# HARDCAL1_REVA_PG2.net
KiCad netlist of a schematic drawn in Altium Designer
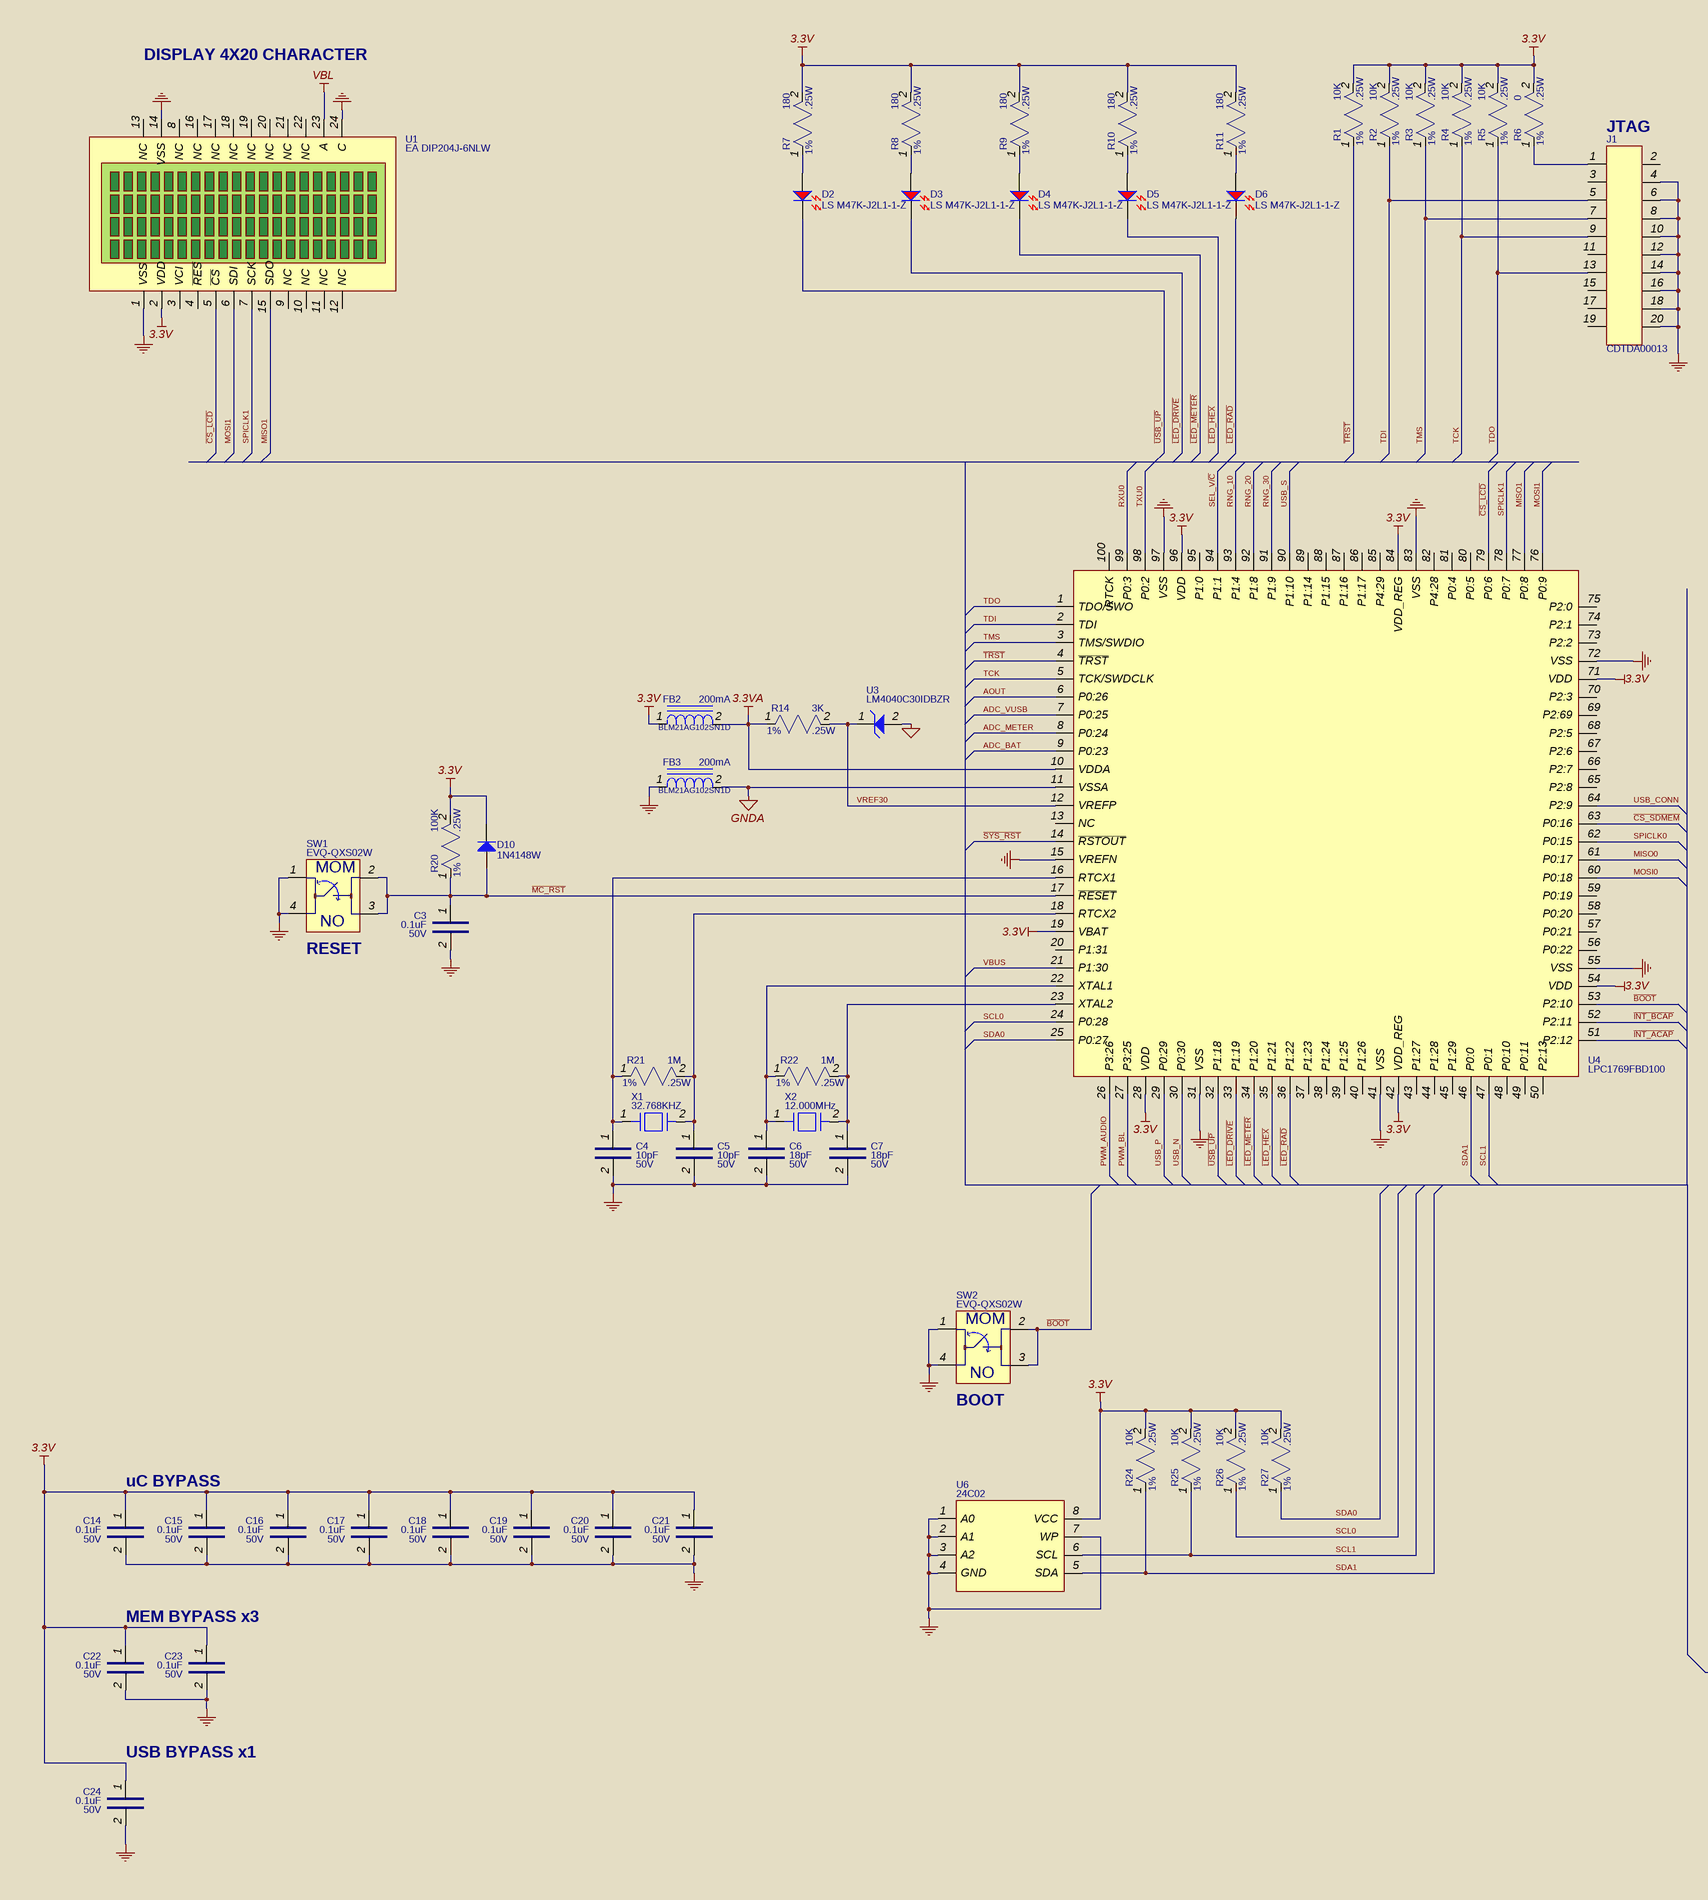
[diagram p0: HARDCAL1_REVA_PG2.SchDoc, left]
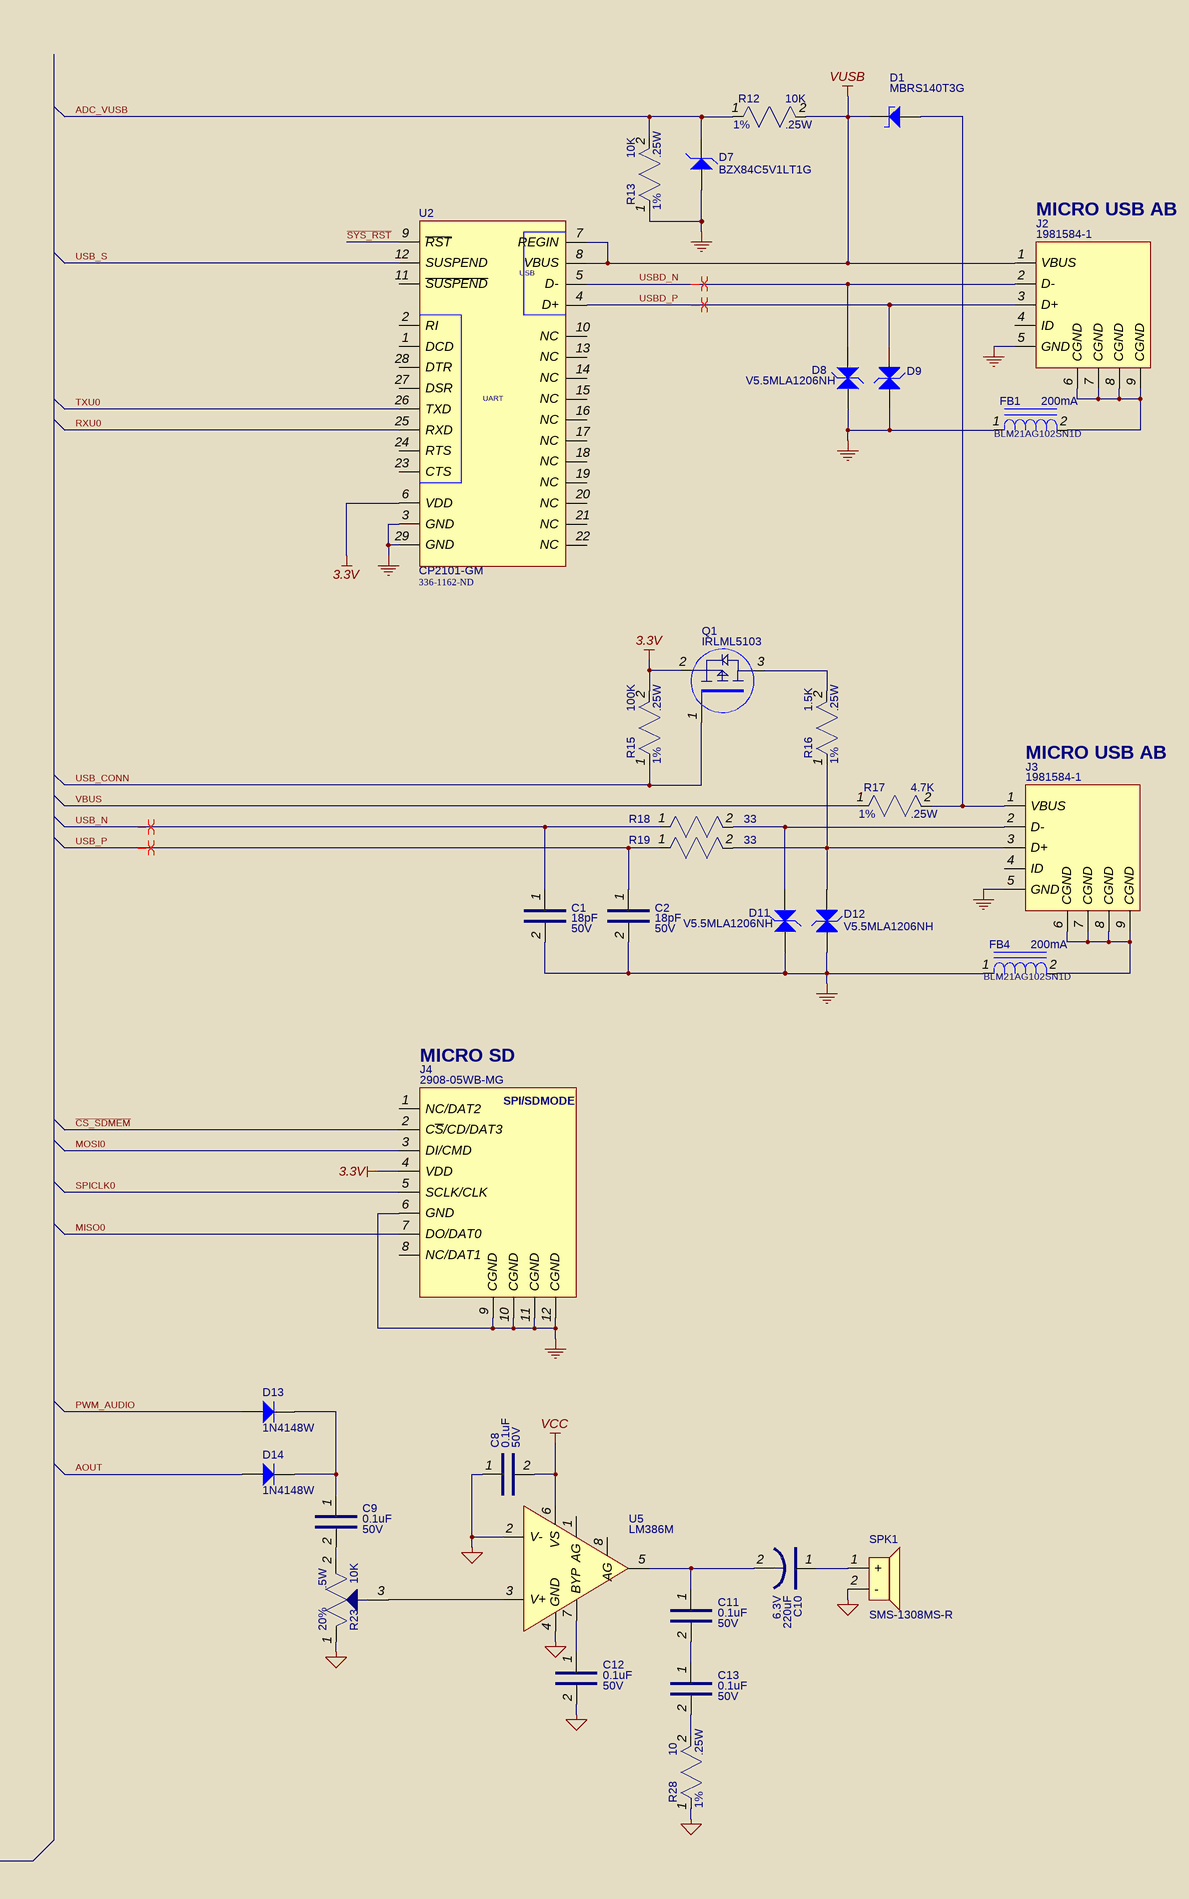
[diagram p1: HARDCAL1_REVA_PG2.SchDoc, right]

(export (version "E")
  (design (tool "Eeschema 10.0.6"))
  (components
    (comp (ref "C1")
      (value "18pF")
      (footprint "3216[1206] - TAN COLOR")
      (description "CAP, CERAMIC, NPO, 18PF, 50V, 1206, 5%, RoHS")
      (fields (field (name "MFG") "YAGEO") (field (name "TOLERANCE") "10%") (field (name "VOLTAGE") "50V"))
      (libsource (lib "HabLib") (part "CDECA00095"))
    )
    (comp (ref "C2")
      (value "18pF")
      (footprint "3216[1206] - TAN COLOR")
      (description "CAP, CERAMIC, NPO, 18PF, 50V, 1206, 5%, RoHS")
      (fields (field (name "MFG") "YAGEO") (field (name "TOLERANCE") "10%") (field (name "VOLTAGE") "50V"))
      (libsource (lib "HabLib") (part "CDECA00095"))
    )
    (comp (ref "C3")
      (value "0.1uF")
      (footprint "3216[1206] - TAN COLOR")
      (description "CAP, CERAMIC CHIP 0.1UF 10% 50V X7R ROHS")
      (fields (field (name "MFG") "AVX") (field (name "TOLERANCE") "10%") (field (name "VOLTAGE") "50V"))
      (libsource (lib "HabLib") (part "CDECA00070"))
    )
    (comp (ref "C4")
      (value "10pF")
      (footprint "3216[1206] - TAN COLOR")
      (description "CAP, CERAMIC, NPO, 10PF, 50V, 1206, 5%, RoHS")
      (fields (field (name "MFG") "AVX") (field (name "TOLERANCE") "10%") (field (name "VOLTAGE") "50V"))
      (libsource (lib "HabLib") (part "CDECA00143"))
    )
    (comp (ref "C5")
      (value "10pF")
      (footprint "3216[1206] - TAN COLOR")
      (description "CAP, CERAMIC, NPO, 10PF, 50V, 1206, 5%, RoHS")
      (fields (field (name "MFG") "AVX") (field (name "TOLERANCE") "10%") (field (name "VOLTAGE") "50V"))
      (libsource (lib "HabLib") (part "CDECA00143"))
    )
    (comp (ref "C6")
      (value "18pF")
      (footprint "3216[1206] - TAN COLOR")
      (description "CAP, CERAMIC, NPO, 18PF, 50V, 1206, 5%, RoHS")
      (fields (field (name "MFG") "YAGEO") (field (name "TOLERANCE") "10%") (field (name "VOLTAGE") "50V"))
      (libsource (lib "HabLib") (part "CDECA00095"))
    )
    (comp (ref "C7")
      (value "18pF")
      (footprint "3216[1206] - TAN COLOR")
      (description "CAP, CERAMIC, NPO, 18PF, 50V, 1206, 5%, RoHS")
      (fields (field (name "MFG") "YAGEO") (field (name "TOLERANCE") "10%") (field (name "VOLTAGE") "50V"))
      (libsource (lib "HabLib") (part "CDECA00095"))
    )
    (comp (ref "C8")
      (value "0.1uF")
      (footprint "3216[1206] - TAN COLOR")
      (description "CAP, CERAMIC CHIP 0.1UF 10% 50V X7R ROHS")
      (fields (field (name "MFG") "AVX") (field (name "TOLERANCE") "10%") (field (name "VOLTAGE") "50V"))
      (libsource (lib "HabLib") (part "CDECA00070"))
    )
    (comp (ref "C9")
      (value "0.1uF")
      (footprint "3216[1206] - TAN COLOR")
      (description "CAP, CERAMIC CHIP 0.1UF 10% 50V X7R ROHS")
      (fields (field (name "MFG") "AVX") (field (name "TOLERANCE") "10%") (field (name "VOLTAGE") "50V"))
      (libsource (lib "HabLib") (part "CDECA00070"))
    )
    (comp (ref "C10")
      (value "220uF")
      (footprint "CAP_TANT_3528")
      (description "CAP, TANT, 220UF, 6.3V, 20%, LOW ESR, 3528, ROHS")
      (fields (field (name "MFG") "KEMET") (field (name "TOLERANCE") "20%") (field (name "VOLTAGE") "6.3V"))
      (libsource (lib "HabLib") (part "CDECA00139_2"))
    )
    (comp (ref "C11")
      (value "0.1uF")
      (footprint "3216[1206] - TAN COLOR")
      (description "CAP, CERAMIC CHIP 0.1UF 10% 50V X7R ROHS")
      (fields (field (name "MFG") "AVX") (field (name "TOLERANCE") "10%") (field (name "VOLTAGE") "50V"))
      (libsource (lib "HabLib") (part "CDECA00070"))
    )
    (comp (ref "C12")
      (value "0.1uF")
      (footprint "3216[1206] - TAN COLOR")
      (description "CAP, CERAMIC CHIP 0.1UF 10% 50V X7R ROHS")
      (fields (field (name "MFG") "AVX") (field (name "TOLERANCE") "10%") (field (name "VOLTAGE") "50V"))
      (libsource (lib "HabLib") (part "CDECA00070"))
    )
    (comp (ref "C13")
      (value "0.1uF")
      (footprint "3216[1206] - TAN COLOR")
      (description "CAP, CERAMIC CHIP 0.1UF 10% 50V X7R ROHS")
      (fields (field (name "MFG") "AVX") (field (name "TOLERANCE") "10%") (field (name "VOLTAGE") "50V"))
      (libsource (lib "HabLib") (part "CDECA00070"))
    )
    (comp (ref "C14")
      (value "0.1uF")
      (footprint "3216[1206] - TAN COLOR")
      (description "CAP, CERAMIC CHIP 0.1UF 10% 50V X7R ROHS")
      (fields (field (name "MFG") "AVX") (field (name "TOLERANCE") "10%") (field (name "VOLTAGE") "50V"))
      (libsource (lib "HabLib") (part "CDECA00070"))
    )
    (comp (ref "C15")
      (value "0.1uF")
      (footprint "3216[1206] - TAN COLOR")
      (description "CAP, CERAMIC CHIP 0.1UF 10% 50V X7R ROHS")
      (fields (field (name "MFG") "AVX") (field (name "TOLERANCE") "10%") (field (name "VOLTAGE") "50V"))
      (libsource (lib "HabLib") (part "CDECA00070"))
    )
    (comp (ref "C16")
      (value "0.1uF")
      (footprint "3216[1206] - TAN COLOR")
      (description "CAP, CERAMIC CHIP 0.1UF 10% 50V X7R ROHS")
      (fields (field (name "MFG") "AVX") (field (name "TOLERANCE") "10%") (field (name "VOLTAGE") "50V"))
      (libsource (lib "HabLib") (part "CDECA00070"))
    )
    (comp (ref "C17")
      (value "0.1uF")
      (footprint "3216[1206] - TAN COLOR")
      (description "CAP, CERAMIC CHIP 0.1UF 10% 50V X7R ROHS")
      (fields (field (name "MFG") "AVX") (field (name "TOLERANCE") "10%") (field (name "VOLTAGE") "50V"))
      (libsource (lib "HabLib") (part "CDECA00070"))
    )
    (comp (ref "C18")
      (value "0.1uF")
      (footprint "3216[1206] - TAN COLOR")
      (description "CAP, CERAMIC CHIP 0.1UF 10% 50V X7R ROHS")
      (fields (field (name "MFG") "AVX") (field (name "TOLERANCE") "10%") (field (name "VOLTAGE") "50V"))
      (libsource (lib "HabLib") (part "CDECA00070"))
    )
    (comp (ref "C19")
      (value "0.1uF")
      (footprint "3216[1206] - TAN COLOR")
      (description "CAP, CERAMIC CHIP 0.1UF 10% 50V X7R ROHS")
      (fields (field (name "MFG") "AVX") (field (name "TOLERANCE") "10%") (field (name "VOLTAGE") "50V"))
      (libsource (lib "HabLib") (part "CDECA00070"))
    )
    (comp (ref "C20")
      (value "0.1uF")
      (footprint "3216[1206] - TAN COLOR")
      (description "CAP, CERAMIC CHIP 0.1UF 10% 50V X7R ROHS")
      (fields (field (name "MFG") "AVX") (field (name "TOLERANCE") "10%") (field (name "VOLTAGE") "50V"))
      (libsource (lib "HabLib") (part "CDECA00070"))
    )
    (comp (ref "C21")
      (value "0.1uF")
      (footprint "3216[1206] - TAN COLOR")
      (description "CAP, CERAMIC CHIP 0.1UF 10% 50V X7R ROHS")
      (fields (field (name "MFG") "AVX") (field (name "TOLERANCE") "10%") (field (name "VOLTAGE") "50V"))
      (libsource (lib "HabLib") (part "CDECA00070"))
    )
    (comp (ref "C22")
      (value "0.1uF")
      (footprint "3216[1206] - TAN COLOR")
      (description "CAP, CERAMIC CHIP 0.1UF 10% 50V X7R ROHS")
      (fields (field (name "MFG") "AVX") (field (name "TOLERANCE") "10%") (field (name "VOLTAGE") "50V"))
      (libsource (lib "HabLib") (part "CDECA00070"))
    )
    (comp (ref "C23")
      (value "0.1uF")
      (footprint "3216[1206] - TAN COLOR")
      (description "CAP, CERAMIC CHIP 0.1UF 10% 50V X7R ROHS")
      (fields (field (name "MFG") "AVX") (field (name "TOLERANCE") "10%") (field (name "VOLTAGE") "50V"))
      (libsource (lib "HabLib") (part "CDECA00070"))
    )
    (comp (ref "C24")
      (value "0.1uF")
      (footprint "3216[1206] - TAN COLOR")
      (description "CAP, CERAMIC CHIP 0.1UF 10% 50V X7R ROHS")
      (fields (field (name "MFG") "AVX") (field (name "TOLERANCE") "10%") (field (name "VOLTAGE") "50V"))
      (libsource (lib "HabLib") (part "CDECA00070"))
    )
    (comp (ref "D1")
      (value "MBRS140T3G")
      (footprint "DIODE_SMB")
      (description "Diode, Schottky rectifier, 40V, 1A, SMB package, Pb free")
      (fields
        (field (name "MFG") "ON SEMICONDUCTOR")
        (field (name "Comment") "CDEDA00019")
        (field (name "PUBLISHER") "Altium Limited")
      )
      (libsource (lib "HabLib") (part "CDEDA00019"))
    )
    (comp (ref "D2")
      (value "LS M47K-J2L1-1-Z")
      (footprint "OSRAM_XX_M47K")
      (description "DIODE,LED RED UNDER MOUNT SM VF=1.8 I=2MA ROHS")
      (fields (field (name "MFG") "OSRAM") (field (name "Comment") "CDELA00019_1"))
      (libsource (lib "HabLib") (part "CDELA00019_1"))
    )
    (comp (ref "D3")
      (value "LS M47K-J2L1-1-Z")
      (footprint "OSRAM_XX_M47K")
      (description "DIODE,LED RED UNDER MOUNT SM VF=1.8 I=2MA ROHS")
      (fields (field (name "MFG") "OSRAM") (field (name "Comment") "CDELA00019_1"))
      (libsource (lib "HabLib") (part "CDELA00019_1"))
    )
    (comp (ref "D4")
      (value "LS M47K-J2L1-1-Z")
      (footprint "OSRAM_XX_M47K")
      (description "DIODE,LED RED UNDER MOUNT SM VF=1.8 I=2MA ROHS")
      (fields (field (name "MFG") "OSRAM") (field (name "Comment") "CDELA00019_1"))
      (libsource (lib "HabLib") (part "CDELA00019_1"))
    )
    (comp (ref "D5")
      (value "LS M47K-J2L1-1-Z")
      (footprint "OSRAM_XX_M47K")
      (description "DIODE,LED RED UNDER MOUNT SM VF=1.8 I=2MA ROHS")
      (fields (field (name "MFG") "OSRAM") (field (name "Comment") "CDELA00019_1"))
      (libsource (lib "HabLib") (part "CDELA00019_1"))
    )
    (comp (ref "D6")
      (value "LS M47K-J2L1-1-Z")
      (footprint "OSRAM_XX_M47K")
      (description "DIODE,LED RED UNDER MOUNT SM VF=1.8 I=2MA ROHS")
      (fields (field (name "MFG") "OSRAM") (field (name "Comment") "CDELA00019_1"))
      (libsource (lib "HabLib") (part "CDELA00019_1"))
    )
    (comp (ref "D7")
      (value "BZX84C5V1LT1G")
      (footprint "SOT23 - TRANSISTOR")
      (description "DIODE, ZENER, 5.1V, 225MW, SOT-23, ROHS")
      (fields
        (field (name "MFG") "ON SEMICONDUCTOR")
        (field (name "Comment") "CDEDA00043")
        (field (name "PUBLISHER") "Altium Limited")
      )
      (libsource (lib "HabLib") (part "CDEDA00043"))
    )
    (comp (ref "D8")
      (value "V5.5MLA1206NH")
      (footprint "3216[1206]")
      (description "VARISTOR, TVS, 5.5VDC, 1206, 150A, .60J, RoHS")
      (fields (field (name "MFG") "LITTLEFUSE") (field (name "MANUFACTURER") "Littelfuse Inc"))
      (libsource (lib "HabLib") (part "CDEDA00037_1"))
    )
    (comp (ref "D9")
      (value "CDEDA00037_1")
      (footprint "3216[1206]")
      (description "VARISTOR, TVS, 5.5VDC, 1206, 150A, .60J, RoHS")
      (fields (field (name "MFG") "LITTLEFUSE") (field (name "MANUFACTURER") "Littelfuse Inc"))
      (libsource (lib "HabLib") (part "CDEDA00037_1"))
    )
    (comp (ref "D10")
      (value "1N4148W")
      (footprint "HabLib:SOD123")
      (description "DIODE, 150MA, 100V, SOD123")
      (fields
        (field (name "MFG") "DIODES INC")
        (field (name "Comment") "CDEDA00020")
        (field (name "PUBLISHER") "Altium Limited")
      )
      (libsource (lib "HabLib") (part "CDEDA00020"))
    )
    (comp (ref "D11")
      (value "V5.5MLA1206NH")
      (footprint "3216[1206]")
      (description "VARISTOR, TVS, 5.5VDC, 1206, 150A, .60J, RoHS")
      (fields (field (name "MFG") "LITTLEFUSE") (field (name "MANUFACTURER") "Littelfuse Inc"))
      (libsource (lib "HabLib") (part "CDEDA00037_1"))
    )
    (comp (ref "D12")
      (value "V5.5MLA1206NH")
      (footprint "3216[1206]")
      (description "VARISTOR, TVS, 5.5VDC, 1206, 150A, .60J, RoHS")
      (fields (field (name "MFG") "LITTLEFUSE") (field (name "MANUFACTURER") "Littelfuse Inc"))
      (libsource (lib "HabLib") (part "CDEDA00037_1"))
    )
    (comp (ref "D13")
      (value "1N4148W")
      (footprint "SOD123")
      (description "DIODE, 150MA, 100V, SOD123")
      (fields (field (name "MFG") "DIODES INC") (field (name "Comment") "CDEDA00020"))
      (libsource (lib "HabLib") (part "CDEDA00020"))
    )
    (comp (ref "D14")
      (value "1N4148W")
      (footprint "SOD123")
      (description "DIODE, 150MA, 100V, SOD123")
      (fields (field (name "MFG") "DIODES INC") (field (name "Comment") "CDEDA00020"))
      (libsource (lib "HabLib") (part "CDEDA00020"))
    )
    (comp (ref "FB1")
      (value "CDEVA00115")
      (footprint "2012[0805]")
      (description "FERRITE, 1KOHM AT 100MHZ, 220MA, .450DCR")
      (fields
        (field (name "MFG") "MURATA")
        (field (name "TOLERANCE") "10%")
        (field (name "MFG_PN") "BLM21AG102SN1D")
        (field (name "POWER") "200mA")
        (field (name "PUBLISHER") "Altium Limited")
      )
      (libsource (lib "HabLib") (part "CDEVA00115"))
    )
    (comp (ref "FB2")
      (value "CDEVA00115")
      (footprint "2012[0805]")
      (description "FERRITE, 1KOHM AT 100MHZ, 220MA, .450DCR")
      (fields
        (field (name "MFG") "MURATA")
        (field (name "TOLERANCE") "10%")
        (field (name "MFG_PN") "BLM21AG102SN1D")
        (field (name "POWER") "200mA")
        (field (name "PUBLISHER") "Altium Limited")
      )
      (libsource (lib "HabLib") (part "CDEVA00115"))
    )
    (comp (ref "FB3")
      (value "CDEVA00115")
      (footprint "2012[0805]")
      (description "FERRITE, 1KOHM AT 100MHZ, 220MA, .450DCR")
      (fields
        (field (name "MFG") "MURATA")
        (field (name "TOLERANCE") "10%")
        (field (name "MFG_PN") "BLM21AG102SN1D")
        (field (name "POWER") "200mA")
        (field (name "PUBLISHER") "Altium Limited")
      )
      (libsource (lib "HabLib") (part "CDEVA00115"))
    )
    (comp (ref "FB4")
      (value "CDEVA00115")
      (footprint "2012[0805]")
      (description "FERRITE, 1KOHM AT 100MHZ, 220MA, .450DCR")
      (fields
        (field (name "MFG") "MURATA")
        (field (name "TOLERANCE") "10%")
        (field (name "MFG_PN") "BLM21AG102SN1D")
        (field (name "POWER") "200mA")
        (field (name "PUBLISHER") "Altium Limited")
      )
      (libsource (lib "HabLib") (part "CDEVA00115"))
    )
    (comp (ref "J1")
      (value "CDTDA00013")
      (footprint "HDR_2X10_100MIL")
      (description "CONN, HDR, 2X10, 100MIL, TH, ROHS")
      (fields (field (name "MFG") "TYCO ELECTRONICS"))
      (libsource (lib "HabLib") (part "CDTDA00013"))
    )
    (comp (ref "J2")
      (value "1981584-1")
      (footprint "TYCO_1981584-1")
      (description "CONN, RCPTL MICRO USB TYPE AB, SM RA")
      (fields (field (name "MFG") "TYCO") (field (name "Comment") "CDTDA_1"))
      (libsource (lib "HabLib") (part "CDTDA_1"))
    )
    (comp (ref "J3")
      (value "1981584-1")
      (footprint "TYCO_1981584-1")
      (description "CONN, RCPTL MICRO USB TYPE AB, SM RA")
      (fields (field (name "MFG") "TYCO") (field (name "Comment") "CDTDA_1"))
      (libsource (lib "HabLib") (part "CDTDA_1"))
    )
    (comp (ref "J4")
      (value "2908-05WB-MG")
      (footprint "3M_2908-05WB-MG")
      (description "CONN, MICRO SD, SM, ROHS")
      (fields (field (name "MFG") "3M") (field (name "Comment") "CDTDA_2"))
      (libsource (lib "HabLib") (part "CDTDA_2"))
    )
    (comp (ref "Q1")
      (value "IRLML5103")
      (footprint "SOT23 - TRANSISTOR")
      (description "MOSFET P CHN, VDS=30V, RDSON = .6OHM, SOT 23")
      (fields
        (field (name "MFG") "INTERNATIONAL RECTIFIER")
        (field (name "Comment") "CDENA00031")
        (field (name "PUBLISHER") "Altium Limited")
      )
      (libsource (lib "HabLib") (part "CDENA00031"))
    )
    (comp (ref "R1")
      (value "10K")
      (footprint "HabLib:3216[1206]")
      (description "RESISTOR, CHIP 1206 10K OHM 1% 1/4W THICK FILM ROHS")
      (fields
        (field (name "MFG") "PANASONIC")
        (field (name "TOLERANCE") "1%")
        (field (name "POWER") ".25W")
        (field (name "Comment") "CDERA00170")
        (field (name "PUBLISHER") "Altium Limited")
      )
      (libsource (lib "HabLib") (part "CDERA00170"))
    )
    (comp (ref "R2")
      (value "10K")
      (footprint "HabLib:3216[1206]")
      (description "RESISTOR, CHIP 1206 10K OHM 1% 1/4W THICK FILM ROHS")
      (fields
        (field (name "MFG") "PANASONIC")
        (field (name "TOLERANCE") "1%")
        (field (name "POWER") ".25W")
        (field (name "Comment") "CDERA00170")
        (field (name "PUBLISHER") "Altium Limited")
      )
      (libsource (lib "HabLib") (part "CDERA00170"))
    )
    (comp (ref "R3")
      (value "10K")
      (footprint "HabLib:3216[1206]")
      (description "RESISTOR, CHIP 1206 10K OHM 1% 1/4W THICK FILM ROHS")
      (fields
        (field (name "MFG") "PANASONIC")
        (field (name "TOLERANCE") "1%")
        (field (name "POWER") ".25W")
        (field (name "Comment") "CDERA00170")
        (field (name "PUBLISHER") "Altium Limited")
      )
      (libsource (lib "HabLib") (part "CDERA00170"))
    )
    (comp (ref "R4")
      (value "10K")
      (footprint "HabLib:3216[1206]")
      (description "RESISTOR, CHIP 1206 10K OHM 1% 1/4W THICK FILM ROHS")
      (fields
        (field (name "MFG") "PANASONIC")
        (field (name "TOLERANCE") "1%")
        (field (name "POWER") ".25W")
        (field (name "Comment") "CDERA00170")
        (field (name "PUBLISHER") "Altium Limited")
      )
      (libsource (lib "HabLib") (part "CDERA00170"))
    )
    (comp (ref "R5")
      (value "10K")
      (footprint "HabLib:3216[1206]")
      (description "RESISTOR, CHIP 1206 10K OHM 1% 1/4W THICK FILM ROHS")
      (fields
        (field (name "MFG") "PANASONIC")
        (field (name "TOLERANCE") "1%")
        (field (name "POWER") ".25W")
        (field (name "Comment") "CDERA00170")
        (field (name "PUBLISHER") "Altium Limited")
      )
      (libsource (lib "HabLib") (part "CDERA00170"))
    )
    (comp (ref "R6")
      (value "0")
      (footprint "HABLIB:3216[1206]")
      (description "RESISTOR, CHIP 1206 0.0 OHM 1% 1/4W THICK FILM ROHS")
      (fields
        (field (name "MFG") "PANASONIC")
        (field (name "TOLERANCE") "1%")
        (field (name "POWER") ".25W")
        (field (name "Comment") "CDERA00181")
        (field (name "PUBLISHER") "Altium Limited")
      )
      (libsource (lib "HabLib") (part "CDERA00181"))
    )
    (comp (ref "R7")
      (value "180")
      (footprint "HABLIB:3216[1206]")
      (description "RESISTOR, CHIP 1206 180 OHM 1% 1/4W THICK FILM ROHS")
      (fields
        (field (name "MFG") "PANASONIC")
        (field (name "TOLERANCE") "1%")
        (field (name "POWER") ".25W")
        (field (name "Comment") "CDERA00192")
        (field (name "PUBLISHER") "Altium Limited")
      )
      (libsource (lib "HabLib") (part "CDERA00192"))
    )
    (comp (ref "R8")
      (value "180")
      (footprint "HABLIB:3216[1206]")
      (description "RESISTOR, CHIP 1206 180 OHM 1% 1/4W THICK FILM ROHS")
      (fields
        (field (name "MFG") "PANASONIC")
        (field (name "TOLERANCE") "1%")
        (field (name "POWER") ".25W")
        (field (name "Comment") "CDERA00192")
        (field (name "PUBLISHER") "Altium Limited")
      )
      (libsource (lib "HabLib") (part "CDERA00192"))
    )
    (comp (ref "R9")
      (value "180")
      (footprint "HABLIB:3216[1206]")
      (description "RESISTOR, CHIP 1206 180 OHM 1% 1/4W THICK FILM ROHS")
      (fields
        (field (name "MFG") "PANASONIC")
        (field (name "TOLERANCE") "1%")
        (field (name "POWER") ".25W")
        (field (name "Comment") "CDERA00192")
        (field (name "PUBLISHER") "Altium Limited")
      )
      (libsource (lib "HabLib") (part "CDERA00192"))
    )
    (comp (ref "R10")
      (value "180")
      (footprint "HABLIB:3216[1206]")
      (description "RESISTOR, CHIP 1206 180 OHM 1% 1/4W THICK FILM ROHS")
      (fields
        (field (name "MFG") "PANASONIC")
        (field (name "TOLERANCE") "1%")
        (field (name "POWER") ".25W")
        (field (name "Comment") "CDERA00192")
        (field (name "PUBLISHER") "Altium Limited")
      )
      (libsource (lib "HabLib") (part "CDERA00192"))
    )
    (comp (ref "R11")
      (value "180")
      (footprint "HABLIB:3216[1206]")
      (description "RESISTOR, CHIP 1206 180 OHM 1% 1/4W THICK FILM ROHS")
      (fields
        (field (name "MFG") "PANASONIC")
        (field (name "TOLERANCE") "1%")
        (field (name "POWER") ".25W")
        (field (name "Comment") "CDERA00192")
        (field (name "PUBLISHER") "Altium Limited")
      )
      (libsource (lib "HabLib") (part "CDERA00192"))
    )
    (comp (ref "R12")
      (value "10K")
      (footprint "HabLib:3216[1206]")
      (description "RESISTOR, CHIP 1206 10K OHM 1% 1/4W THICK FILM ROHS")
      (fields
        (field (name "MFG") "PANASONIC")
        (field (name "TOLERANCE") "1%")
        (field (name "POWER") ".25W")
        (field (name "Comment") "CDERA00170")
        (field (name "PUBLISHER") "Altium Limited")
      )
      (libsource (lib "HabLib") (part "CDERA00170"))
    )
    (comp (ref "R13")
      (value "10K")
      (footprint "HabLib:3216[1206]")
      (description "RESISTOR, CHIP 1206 10K OHM 1% 1/4W THICK FILM ROHS")
      (fields
        (field (name "MFG") "PANASONIC")
        (field (name "TOLERANCE") "1%")
        (field (name "POWER") ".25W")
        (field (name "Comment") "CDERA00170")
        (field (name "PUBLISHER") "Altium Limited")
      )
      (libsource (lib "HabLib") (part "CDERA00170"))
    )
    (comp (ref "R14")
      (value "3K")
      (footprint "HABLIB:3216[1206]")
      (description "RESISTOR, CHIP 1206 3K OHM 1% 1/4W THICK FILM ROHS")
      (fields
        (field (name "MFG") "PANASONIC")
        (field (name "TOLERANCE") "1%")
        (field (name "POWER") ".25W")
        (field (name "Comment") "CDERA00275_9")
        (field (name "PUBLISHER") "Altium Limited")
      )
      (libsource (lib "HabLib") (part "CDERA00275_9"))
    )
    (comp (ref "R15")
      (value "100K")
      (footprint "HABLIB:3216[1206]")
      (description "RESISTOR, CHIP 1206 100K OHM 1% 1/4W THICK FILM ROHS")
      (fields
        (field (name "MFG") "PANASONIC")
        (field (name "TOLERANCE") "1%")
        (field (name "POWER") ".25W")
        (field (name "Comment") "CDERA00198")
        (field (name "PUBLISHER") "Altium Limited")
      )
      (libsource (lib "HabLib") (part "CDERA00198"))
    )
    (comp (ref "R16")
      (value "1.5K")
      (footprint "HabLib:3216[1206]")
      (description "RESISTOR, CHIP 1206 1.5K OHM 1% 1/4W THICK FILM ROHS")
      (fields
        (field (name "MFG") "PANASONIC")
        (field (name "TOLERANCE") "1%")
        (field (name "POWER") ".25W")
        (field (name "Comment") "CDERA00179")
        (field (name "PUBLISHER") "Altium Limited")
      )
      (libsource (lib "HabLib") (part "CDERA00179"))
    )
    (comp (ref "R17")
      (value "4.7K")
      (footprint "HABLIB:3216[1206]")
      (description "RESISTOR, CHIP 1206 4.7K OHM 1% 1/4W THICK FILM ROHS")
      (fields
        (field (name "MFG") "PANASONIC")
        (field (name "TOLERANCE") "1%")
        (field (name "POWER") ".25W")
        (field (name "Comment") "CDERA00169")
        (field (name "PUBLISHER") "Altium Limited")
      )
      (libsource (lib "HabLib") (part "CDERA00169"))
    )
    (comp (ref "R18")
      (value "33")
      (footprint "HABLIB:3216[1206]")
      (description "RESISTOR, CHIP 1206 33 OHM 1% 1/4W THICK FILM ROHS")
      (fields (field (name "MFG") "PANASONIC") (field (name "TOLERANCE") "1%"))
      (libsource (lib "HabLib") (part "CDERA00207"))
    )
    (comp (ref "R19")
      (value "33")
      (footprint "HABLIB:3216[1206]")
      (description "RESISTOR, CHIP 1206 33 OHM 1% 1/4W THICK FILM ROHS")
      (fields (field (name "MFG") "PANASONIC") (field (name "TOLERANCE") "1%"))
      (libsource (lib "HabLib") (part "CDERA00207"))
    )
    (comp (ref "R20")
      (value "100K")
      (footprint "HABLIB:3216[1206]")
      (description "RESISTOR, CHIP 1206 100K OHM 1% 1/4W THICK FILM ROHS")
      (fields
        (field (name "MFG") "PANASONIC")
        (field (name "TOLERANCE") "1%")
        (field (name "POWER") ".25W")
        (field (name "Comment") "CDERA00198")
        (field (name "PUBLISHER") "Altium Limited")
      )
      (libsource (lib "HabLib") (part "CDERA00198"))
    )
    (comp (ref "R21")
      (value "1M")
      (footprint "HABLIB:3216[1206]")
      (description "RESISTOR, CHIP 1206 1MOHM 1% 1/4W THICK FILM ROHS")
      (fields
        (field (name "MFG") "PANASONIC")
        (field (name "TOLERANCE") "1%")
        (field (name "POWER") ".25W")
        (field (name "Comment") "CDERA00191")
        (field (name "PUBLISHER") "Altium Limited")
      )
      (libsource (lib "HabLib") (part "CDERA00191"))
    )
    (comp (ref "R22")
      (value "1M")
      (footprint "HABLIB:3216[1206]")
      (description "RESISTOR, CHIP 1206 1MOHM 1% 1/4W THICK FILM ROHS")
      (fields
        (field (name "MFG") "PANASONIC")
        (field (name "TOLERANCE") "1%")
        (field (name "POWER") ".25W")
        (field (name "Comment") "CDERA00191")
        (field (name "PUBLISHER") "Altium Limited")
      )
      (libsource (lib "HabLib") (part "CDERA00191"))
    )
    (comp (ref "R23")
      (value "10K")
      (footprint "BOURNS_3352")
      (description "RESISTOR, POT 10K OHM 20% THUMBWHELL, CERM, TH, ROHS")
      (fields
        (field (name "MFG") "BOURNS")
        (field (name "TOLERANCE") "20%")
        (field (name "POWER") ".5W")
        (field (name "Comment") "CDERA00207_2")
      )
      (libsource (lib "HabLib") (part "CDERA00207_2"))
    )
    (comp (ref "R24")
      (value "10K")
      (footprint "HabLib:3216[1206]")
      (description "RESISTOR, CHIP 1206 10K OHM 1% 1/4W THICK FILM ROHS")
      (fields
        (field (name "MFG") "PANASONIC")
        (field (name "TOLERANCE") "1%")
        (field (name "POWER") ".25W")
        (field (name "Comment") "CDERA00170")
        (field (name "PUBLISHER") "Altium Limited")
      )
      (libsource (lib "HabLib") (part "CDERA00170"))
    )
    (comp (ref "R25")
      (value "10K")
      (footprint "HabLib:3216[1206]")
      (description "RESISTOR, CHIP 1206 10K OHM 1% 1/4W THICK FILM ROHS")
      (fields
        (field (name "MFG") "PANASONIC")
        (field (name "TOLERANCE") "1%")
        (field (name "POWER") ".25W")
        (field (name "Comment") "CDERA00170")
        (field (name "PUBLISHER") "Altium Limited")
      )
      (libsource (lib "HabLib") (part "CDERA00170"))
    )
    (comp (ref "R26")
      (value "10K")
      (footprint "HabLib:3216[1206]")
      (description "RESISTOR, CHIP 1206 10K OHM 1% 1/4W THICK FILM ROHS")
      (fields
        (field (name "MFG") "PANASONIC")
        (field (name "TOLERANCE") "1%")
        (field (name "POWER") ".25W")
        (field (name "Comment") "CDERA00170")
        (field (name "PUBLISHER") "Altium Limited")
      )
      (libsource (lib "HabLib") (part "CDERA00170"))
    )
    (comp (ref "R27")
      (value "10K")
      (footprint "HabLib:3216[1206]")
      (description "RESISTOR, CHIP 1206 10K OHM 1% 1/4W THICK FILM ROHS")
      (fields
        (field (name "MFG") "PANASONIC")
        (field (name "TOLERANCE") "1%")
        (field (name "POWER") ".25W")
        (field (name "Comment") "CDERA00170")
        (field (name "PUBLISHER") "Altium Limited")
      )
      (libsource (lib "HabLib") (part "CDERA00170"))
    )
    (comp (ref "R28")
      (value "10")
      (footprint "HABLIB:3216[1206]")
      (description "RESISTOR, CHIP 1206 10 OHM 1% 1/4W THICK FILM ROHS")
      (fields
        (field (name "MFG") "PANASONIC")
        (field (name "TOLERANCE") "1%")
        (field (name "POWER") ".25W")
        (field (name "Comment") "CDERA00142")
      )
      (libsource (lib "HabLib") (part "CDERA00142"))
    )
    (comp (ref "SPK1")
      (value "CDEVA_2")
      (footprint "PUI_AUDIO_SMS-1308MS-R")
      (description "SPEAKER 8OHM .7W 88DB 13MM SMD")
      (fields (field (name "MFG") "PUI AUDIO") (field (name "MFG_PN") "SMS-1308MS-R"))
      (libsource (lib "HabLib") (part "CDEVA_2"))
    )
    (comp (ref "SW1")
      (value "EVQ-QXS02W")
      (footprint "PANASONIC_EVQQX")
      (description "SWITCH, MOM, NO, SM")
      (fields
        (field (name "MFG") "PANASONIC")
        (field (name "Comment") "CDESA00095")
        (field (name "PUBLISHER") "Altium Limited")
      )
      (libsource (lib "HabLib") (part "CDESA00095"))
    )
    (comp (ref "SW2")
      (value "EVQ-QXS02W")
      (footprint "PANASONIC_EVQQX")
      (description "SWITCH, MOM, NO, SM")
      (fields
        (field (name "MFG") "PANASONIC")
        (field (name "Comment") "CDESA00095")
        (field (name "PUBLISHER") "Altium Limited")
      )
      (libsource (lib "HabLib") (part "CDESA00095"))
    )
    (comp (ref "U1")
      (value "EA DIP204J-6NLW")
      (footprint "EA_790-EADIP204J6NLW")
      (description "LCD, 4X20 WITH ICONS, SERIAL INTERFACE, 5X8DOT, WHITE BACKLIGHT")
      (fields (field (name "MFG") "ELECTRONIC ASSEMBLY") (field (name "Comment") "CDELA00023_1"))
      (libsource (lib "HabLib") (part "CDELA00023_1"))
    )
    (comp (ref "U2")
      (value "CP2101-GM")
      (footprint "QFN50P500X500-28VBM-MODIFIED")
      (description "IC, TXRX USB TO UART BRIDGE, ROHS, 28QFN")
      (fields
        (field (name "MFG") "SILICON LABS")
        (field (name "SUPPLIER PART NUMBER 1") "336-1162-ND")
        (field (name "Comment") "CDEUA00070_1")
      )
      (libsource (lib "HabLib") (part "CDEUA00070_1"))
    )
    (comp (ref "U3")
      (value "LM4040C30IDBZR")
      (footprint "SOT23 - TRANSISTOR")
      (description "IC, SHUNT VOLTAGE REFERENCE")
      (fields (field (name "MFG") "TEXAS INSTRUMENTS") (field (name "Comment") "CDEUA00049"))
      (libsource (lib "HabLib") (part "CDEUA00049"))
    )
    (comp (ref "U4")
      (value "CDEUA00069_2")
      (footprint "SQFP50P1600X1600-100M_MODIFIED")
      (description "IC, MICRO CONTROLLER, 512KB FLASH, 64K, ARM CORTEX M3, 100LQFP")
      (fields (field (name "MFG") "NXP") (field (name "MFG_PN") "LPC1769FBD100"))
      (libsource (lib "HabLib") (part "CDEUA00069_2"))
    )
    (comp (ref "U5")
      (value "LM386M")
      (footprint "MUA08A")
      (description "IC AUDIO AMP, CLASS AB, 325mW, 8SOIC, ROHS")
      (fields (field (name "MFG") "NATIONAL SEMICONDUCTOR") (field (name "Comment") "CDEUA00071_1"))
      (libsource (lib "HabLib") (part "CDEUA00071_1"))
    )
    (comp (ref "U6")
      (value "24C02")
      (footprint "S8_N: Linear Tech SO8 NARROW")
      (description "IC, EEPROM, I2C, 256x8, 8PIN SO8, ROHOS")
      (fields
        (field (name "MFG") "ATMEL")
        (field (name "Comment") "CDEUA00020")
        (field (name "PUBLISHER") "Altium Limited")
      )
      (libsource (lib "HabLib") (part "CDEUA00020"))
    )
    (comp (ref "X1")
      (value "32.768KHZ")
      (footprint "CITIZEN_CMR200T")
      (description "CRYSTAL, 32.768KHZ, 12.5PF, SMT SM CYLINDRICAL CAN")
      (fields (field (name "MFG") "CITIZEN") (field (name "TOLERANCE") "20ppm"))
      (libsource (lib "HabLib") (part "CDEKA00015"))
    )
    (comp (ref "X2")
      (value "12.000MHz")
      (footprint "HC49/US-SM")
      (description "CRYSTAL, 12.000MHZ, 18PF, SMT HC49/US")
      (fields (field (name "MFG") "CITIZEN") (field (name "TOLERANCE") "30ppm"))
      (libsource (lib "HabLib") (part "CDEKA00019"))
    )
  )
  (nets
    (net (code "1") (name "/ADC_BAT") (class "Default")
      (node (ref "U4") (pin "9") (pinfunction "P0:23_9") (pintype "passive"))
    )
    (net (code "2") (name "/ADC_METER") (class "Default")
      (node (ref "U4") (pin "8") (pinfunction "P0:24_8") (pintype "passive"))
    )
    (net (code "3") (name "/ADC_VUSB") (class "Default")
      (node (ref "D7") (pin "3") (pinfunction "K_3") (pintype "passive"))
      (node (ref "R12") (pin "1") (pinfunction "1_1") (pintype "passive"))
      (node (ref "R13") (pin "2") (pinfunction "2_2") (pintype "passive"))
      (node (ref "U4") (pin "7") (pinfunction "P0:25_7") (pintype "passive"))
    )
    (net (code "4") (name "/AOUT") (class "Default")
      (node (ref "D14") (pin "1") (pinfunction "A_1") (pintype "passive"))
      (node (ref "U4") (pin "6") (pinfunction "P0:26_6") (pintype "passive"))
    )
    (net (code "5") (name "/BOOT") (class "Default")
      (node (ref "SW2") (pin "2") (pintype "passive"))
      (node (ref "SW2") (pin "3") (pintype "passive"))
      (node (ref "U4") (pin "53") (pinfunction "P2:10_53") (pintype "passive"))
    )
    (net (code "6") (name "/CS_LCD") (class "Default")
      (node (ref "U1") (pin "5") (pinfunction "CS_5") (pintype "passive"))
      (node (ref "U4") (pin "79") (pinfunction "P0:6_79") (pintype "passive"))
    )
    (net (code "7") (name "/CS_SDMEM") (class "Default")
      (node (ref "J4") (pin "2") (pinfunction "C~{S}/CD/DAT3_2") (pintype "passive"))
      (node (ref "U4") (pin "63") (pinfunction "P0:16_63") (pintype "passive"))
    )
    (net (code "8") (name "/INT_ACAP") (class "Default")
      (node (ref "U4") (pin "51") (pinfunction "P2:12_51") (pintype "passive"))
    )
    (net (code "9") (name "/INT_BCAP") (class "Default")
      (node (ref "U4") (pin "52") (pinfunction "P2:11_52") (pintype "passive"))
    )
    (net (code "10") (name "/LED_DRIVE") (class "Default")
      (node (ref "D3") (pin "2") (pinfunction "K_2") (pintype "passive"))
      (node (ref "U4") (pin "33") (pinfunction "P1:19_33") (pintype "passive"))
    )
    (net (code "11") (name "/LED_HEX") (class "Default")
      (node (ref "D5") (pin "2") (pinfunction "K_2") (pintype "passive"))
      (node (ref "U4") (pin "35") (pinfunction "P1:21_35") (pintype "passive"))
    )
    (net (code "12") (name "/LED_METER") (class "Default")
      (node (ref "D4") (pin "2") (pinfunction "K_2") (pintype "passive"))
      (node (ref "U4") (pin "34") (pinfunction "P1:20_34") (pintype "passive"))
    )
    (net (code "13") (name "/LED_RAD") (class "Default")
      (node (ref "D6") (pin "2") (pinfunction "K_2") (pintype "passive"))
      (node (ref "U4") (pin "36") (pinfunction "P1:22_36") (pintype "passive"))
    )
    (net (code "14") (name "/MC_RST") (class "Default")
      (node (ref "C3") (pin "1") (pinfunction "1_1") (pintype "passive"))
      (node (ref "D10") (pin "1") (pinfunction "A_1") (pintype "passive"))
      (node (ref "R20") (pin "1") (pinfunction "1_1") (pintype "passive"))
      (node (ref "SW1") (pin "2") (pintype "passive"))
      (node (ref "SW1") (pin "3") (pintype "passive"))
      (node (ref "U4") (pin "17") (pinfunction "RESET_17") (pintype "passive"))
    )
    (net (code "15") (name "/MISO0") (class "Default")
      (node (ref "J4") (pin "7") (pinfunction "DO/DAT0_7") (pintype "passive"))
      (node (ref "U4") (pin "61") (pinfunction "P0:17_61") (pintype "passive"))
    )
    (net (code "16") (name "/MISO1") (class "Default")
      (node (ref "U1") (pin "15") (pinfunction "SDO_15") (pintype "passive"))
      (node (ref "U4") (pin "77") (pinfunction "P0:8_77") (pintype "passive"))
    )
    (net (code "17") (name "/MOSI0") (class "Default")
      (node (ref "J4") (pin "3") (pinfunction "DI/CMD_3") (pintype "passive"))
      (node (ref "U4") (pin "60") (pinfunction "P0:18_60") (pintype "passive"))
    )
    (net (code "18") (name "/MOSI1") (class "Default")
      (node (ref "U1") (pin "6") (pinfunction "SDI_6") (pintype "passive"))
      (node (ref "U4") (pin "76") (pinfunction "P0:9_76") (pintype "passive"))
    )
    (net (code "19") (name "/PWM_AUDIO") (class "Default")
      (node (ref "D13") (pin "1") (pinfunction "A_1") (pintype "passive"))
      (node (ref "U4") (pin "26") (pinfunction "P3:26_26") (pintype "passive"))
    )
    (net (code "20") (name "/PWM_BL") (class "Default")
      (node (ref "U4") (pin "27") (pinfunction "P3:25_27") (pintype "passive"))
    )
    (net (code "21") (name "/RNG_10") (class "Default")
      (node (ref "U4") (pin "93") (pinfunction "P1:4_93") (pintype "passive"))
    )
    (net (code "22") (name "/RNG_20") (class "Default")
      (node (ref "U4") (pin "92") (pinfunction "P1:8_92") (pintype "passive"))
    )
    (net (code "23") (name "/RNG_30") (class "Default")
      (node (ref "U4") (pin "91") (pinfunction "P1:9_91") (pintype "passive"))
    )
    (net (code "24") (name "/RXU0") (class "Default")
      (node (ref "U2") (pin "25") (pinfunction "RXD_25") (pintype "passive"))
      (node (ref "U4") (pin "99") (pinfunction "P0:3_99") (pintype "passive"))
    )
    (net (code "25") (name "/SCL0") (class "Default")
      (node (ref "R26") (pin "1") (pinfunction "1_1") (pintype "passive"))
      (node (ref "U4") (pin "24") (pinfunction "P0:28_24") (pintype "passive"))
    )
    (net (code "26") (name "/SCL1") (class "Default")
      (node (ref "R25") (pin "1") (pinfunction "1_1") (pintype "passive"))
      (node (ref "U4") (pin "47") (pinfunction "P0:1_47") (pintype "passive"))
      (node (ref "U6") (pin "6") (pinfunction "SCL_6") (pintype "passive"))
    )
    (net (code "27") (name "/SDA0") (class "Default")
      (node (ref "R27") (pin "1") (pinfunction "1_1") (pintype "passive"))
      (node (ref "U4") (pin "25") (pinfunction "P0:27_25") (pintype "passive"))
    )
    (net (code "28") (name "/SDA1") (class "Default")
      (node (ref "R24") (pin "1") (pinfunction "1_1") (pintype "passive"))
      (node (ref "U4") (pin "46") (pinfunction "P0:0_46") (pintype "passive"))
      (node (ref "U6") (pin "5") (pinfunction "SDA_5") (pintype "passive"))
    )
    (net (code "29") (name "/SEL_V{slash}~{C}") (class "Default")
      (node (ref "U4") (pin "94") (pinfunction "P1:1_94") (pintype "passive"))
    )
    (net (code "30") (name "/SPICLK0") (class "Default")
      (node (ref "J4") (pin "5") (pinfunction "SCLK/CLK_5") (pintype "passive"))
      (node (ref "U4") (pin "62") (pinfunction "P0:15_62") (pintype "passive"))
    )
    (net (code "31") (name "/SPICLK1") (class "Default")
      (node (ref "U1") (pin "7") (pinfunction "SCK_7") (pintype "passive"))
      (node (ref "U4") (pin "78") (pinfunction "P0:7_78") (pintype "passive"))
    )
    (net (code "32") (name "/SYS_RST") (class "Default")
      (node (ref "U2") (pin "9") (pinfunction "RST_9") (pintype "passive"))
      (node (ref "U4") (pin "14") (pinfunction "RSTOUT_14") (pintype "passive"))
    )
    (net (code "33") (name "/TCK") (class "Default")
      (node (ref "J1") (pin "9") (pinfunction "9_9") (pintype "passive"))
      (node (ref "R4") (pin "1") (pinfunction "1_1") (pintype "passive"))
      (node (ref "U4") (pin "5") (pinfunction "TCK/SWDCLK_5") (pintype "passive"))
    )
    (net (code "34") (name "/TDI") (class "Default")
      (node (ref "J1") (pin "5") (pinfunction "5_5") (pintype "passive"))
      (node (ref "R2") (pin "1") (pinfunction "1_1") (pintype "passive"))
      (node (ref "U4") (pin "2") (pinfunction "TDI_2") (pintype "passive"))
    )
    (net (code "35") (name "/TDO") (class "Default")
      (node (ref "J1") (pin "13") (pinfunction "13_13") (pintype "passive"))
      (node (ref "R5") (pin "1") (pinfunction "1_1") (pintype "passive"))
      (node (ref "U4") (pin "1") (pinfunction "TDO/SWO_1") (pintype "passive"))
    )
    (net (code "36") (name "/TMS") (class "Default")
      (node (ref "J1") (pin "7") (pinfunction "7_7") (pintype "passive"))
      (node (ref "R3") (pin "1") (pinfunction "1_1") (pintype "passive"))
      (node (ref "U4") (pin "3") (pinfunction "TMS/SWDIO_3") (pintype "passive"))
    )
    (net (code "37") (name "/TRST") (class "Default")
      (node (ref "R1") (pin "1") (pinfunction "1_1") (pintype "passive"))
      (node (ref "U4") (pin "4") (pinfunction "TRST_4") (pintype "passive"))
    )
    (net (code "38") (name "/TXU0") (class "Default")
      (node (ref "U2") (pin "26") (pinfunction "TXD_26") (pintype "passive"))
      (node (ref "U4") (pin "98") (pinfunction "P0:2_98") (pintype "passive"))
    )
    (net (code "39") (name "/USBD_N") (class "Default")
      (node (ref "D8") (pin "2") (pinfunction "K_2") (pintype "passive"))
      (node (ref "J2") (pin "2") (pinfunction "D-_2") (pintype "passive"))
      (node (ref "U2") (pin "5") (pinfunction "D-_5") (pintype "passive"))
    )
    (net (code "40") (name "/USBD_P") (class "Default")
      (node (ref "D9") (pin "2") (pinfunction "K_2") (pintype "passive"))
      (node (ref "J2") (pin "3") (pinfunction "D+_3") (pintype "passive"))
      (node (ref "U2") (pin "4") (pinfunction "D+_4") (pintype "passive"))
    )
    (net (code "41") (name "/USB_CONN") (class "Default")
      (node (ref "Q1") (pin "1") (pinfunction "B_1") (pintype "passive"))
      (node (ref "R15") (pin "1") (pinfunction "1_1") (pintype "passive"))
      (node (ref "U4") (pin "64") (pinfunction "P2:9_64") (pintype "passive"))
    )
    (net (code "42") (name "/USB_N") (class "Default")
      (node (ref "C1") (pin "1") (pinfunction "1_1") (pintype "passive"))
      (node (ref "R18") (pin "1") (pinfunction "1_1") (pintype "passive"))
      (node (ref "U4") (pin "30") (pinfunction "P0:30_30") (pintype "passive"))
    )
    (net (code "43") (name "/USB_P") (class "Default")
      (node (ref "C2") (pin "1") (pinfunction "1_1") (pintype "passive"))
      (node (ref "R19") (pin "1") (pinfunction "1_1") (pintype "passive"))
      (node (ref "U4") (pin "29") (pinfunction "P0:29_29") (pintype "passive"))
    )
    (net (code "44") (name "/USB_S") (class "Default")
      (node (ref "U2") (pin "12") (pinfunction "SUSPEND_12") (pintype "passive"))
      (node (ref "U4") (pin "90") (pinfunction "P1:10_90") (pintype "passive"))
    )
    (net (code "45") (name "/USB_UP") (class "Default")
      (node (ref "D2") (pin "2") (pinfunction "K_2") (pintype "passive"))
      (node (ref "U4") (pin "32") (pinfunction "P1:18_32") (pintype "passive"))
    )
    (net (code "46") (name "/VBUS") (class "Default")
      (node (ref "R17") (pin "1") (pinfunction "1_1") (pintype "passive"))
      (node (ref "U4") (pin "21") (pinfunction "P1:30_21") (pintype "passive"))
    )
    (net (code "47") (name "/VREF30") (class "Default")
      (node (ref "R14") (pin "2") (pinfunction "2_2") (pintype "passive"))
      (node (ref "U3") (pin "1") (pinfunction "K_1") (pintype "passive"))
      (node (ref "U4") (pin "12") (pinfunction "VREFP_12") (pintype "passive"))
    )
    (net (code "48") (name "3.3V") (class "Default")
      (node (ref "C14") (pin "1") (pinfunction "1_1") (pintype "passive"))
      (node (ref "C15") (pin "1") (pinfunction "1_1") (pintype "passive"))
      (node (ref "C16") (pin "1") (pinfunction "1_1") (pintype "passive"))
      (node (ref "C17") (pin "1") (pinfunction "1_1") (pintype "passive"))
      (node (ref "C18") (pin "1") (pinfunction "1_1") (pintype "passive"))
      (node (ref "C19") (pin "1") (pinfunction "1_1") (pintype "passive"))
      (node (ref "C20") (pin "1") (pinfunction "1_1") (pintype "passive"))
      (node (ref "C21") (pin "1") (pinfunction "1_1") (pintype "passive"))
      (node (ref "C22") (pin "1") (pinfunction "1_1") (pintype "passive"))
      (node (ref "C23") (pin "1") (pinfunction "1_1") (pintype "passive"))
      (node (ref "C24") (pin "1") (pinfunction "1_1") (pintype "passive"))
      (node (ref "D10") (pin "2") (pinfunction "K_2") (pintype "passive"))
      (node (ref "FB2") (pin "1") (pinfunction "1_1") (pintype "passive"))
      (node (ref "J4") (pin "4") (pinfunction "VDD_4") (pintype "passive"))
      (node (ref "Q1") (pin "2") (pinfunction "E_2") (pintype "passive"))
      (node (ref "R1") (pin "2") (pinfunction "2_2") (pintype "passive"))
      (node (ref "R10") (pin "2") (pinfunction "2_2") (pintype "passive"))
      (node (ref "R11") (pin "2") (pinfunction "2_2") (pintype "passive"))
      (node (ref "R15") (pin "2") (pinfunction "2_2") (pintype "passive"))
      (node (ref "R2") (pin "2") (pinfunction "2_2") (pintype "passive"))
      (node (ref "R20") (pin "2") (pinfunction "2_2") (pintype "passive"))
      (node (ref "R24") (pin "2") (pinfunction "2_2") (pintype "passive"))
      (node (ref "R25") (pin "2") (pinfunction "2_2") (pintype "passive"))
      (node (ref "R26") (pin "2") (pinfunction "2_2") (pintype "passive"))
      (node (ref "R27") (pin "2") (pinfunction "2_2") (pintype "passive"))
      (node (ref "R3") (pin "2") (pinfunction "2_2") (pintype "passive"))
      (node (ref "R4") (pin "2") (pinfunction "2_2") (pintype "passive"))
      (node (ref "R5") (pin "2") (pinfunction "2_2") (pintype "passive"))
      (node (ref "R6") (pin "2") (pinfunction "2_2") (pintype "passive"))
      (node (ref "R7") (pin "2") (pinfunction "2_2") (pintype "passive"))
      (node (ref "R8") (pin "2") (pinfunction "2_2") (pintype "passive"))
      (node (ref "R9") (pin "2") (pinfunction "2_2") (pintype "passive"))
      (node (ref "U1") (pin "2") (pinfunction "VDD_2") (pintype "passive"))
      (node (ref "U2") (pin "6") (pinfunction "VDD_6") (pintype "passive"))
      (node (ref "U4") (pin "19") (pinfunction "VBAT_19") (pintype "passive"))
      (node (ref "U4") (pin "28") (pinfunction "VDD_28") (pintype "passive"))
      (node (ref "U4") (pin "42") (pinfunction "VDD_REG_42") (pintype "passive"))
      (node (ref "U4") (pin "54") (pinfunction "VDD_54") (pintype "passive"))
      (node (ref "U4") (pin "71") (pinfunction "VDD_71") (pintype "passive"))
      (node (ref "U4") (pin "84") (pinfunction "VDD_REG_84") (pintype "passive"))
      (node (ref "U4") (pin "96") (pinfunction "VDD_96") (pintype "passive"))
      (node (ref "U6") (pin "8") (pinfunction "VCC_8") (pintype "passive"))
    )
    (net (code "49") (name "3.3VA") (class "Default")
      (node (ref "FB2") (pin "2") (pinfunction "2_2") (pintype "passive"))
      (node (ref "R14") (pin "1") (pinfunction "1_1") (pintype "passive"))
      (node (ref "U4") (pin "10") (pinfunction "VDDA_10") (pintype "passive"))
    )
    (net (code "50") (name "GND") (class "Default")
      (node (ref "C1") (pin "2") (pinfunction "2_2") (pintype "passive"))
      (node (ref "C14") (pin "2") (pinfunction "2_2") (pintype "passive"))
      (node (ref "C15") (pin "2") (pinfunction "2_2") (pintype "passive"))
      (node (ref "C16") (pin "2") (pinfunction "2_2") (pintype "passive"))
      (node (ref "C17") (pin "2") (pinfunction "2_2") (pintype "passive"))
      (node (ref "C18") (pin "2") (pinfunction "2_2") (pintype "passive"))
      (node (ref "C19") (pin "2") (pinfunction "2_2") (pintype "passive"))
      (node (ref "C2") (pin "2") (pinfunction "2_2") (pintype "passive"))
      (node (ref "C20") (pin "2") (pinfunction "2_2") (pintype "passive"))
      (node (ref "C21") (pin "2") (pinfunction "2_2") (pintype "passive"))
      (node (ref "C22") (pin "2") (pinfunction "2_2") (pintype "passive"))
      (node (ref "C23") (pin "2") (pinfunction "2_2") (pintype "passive"))
      (node (ref "C24") (pin "2") (pinfunction "2_2") (pintype "passive"))
      (node (ref "C3") (pin "2") (pinfunction "2_2") (pintype "passive"))
      (node (ref "C4") (pin "2") (pinfunction "2_2") (pintype "passive"))
      (node (ref "C5") (pin "2") (pinfunction "2_2") (pintype "passive"))
      (node (ref "C6") (pin "2") (pinfunction "2_2") (pintype "passive"))
      (node (ref "C7") (pin "2") (pinfunction "2_2") (pintype "passive"))
      (node (ref "D11") (pin "1") (pinfunction "A_1") (pintype "passive"))
      (node (ref "D12") (pin "1") (pinfunction "A_1") (pintype "passive"))
      (node (ref "D7") (pin "1") (pinfunction "A_1") (pintype "passive"))
      (node (ref "D8") (pin "1") (pinfunction "A_1") (pintype "passive"))
      (node (ref "D9") (pin "1") (pinfunction "A_1") (pintype "passive"))
      (node (ref "FB1") (pin "1") (pinfunction "1_1") (pintype "passive"))
      (node (ref "FB3") (pin "1") (pinfunction "1_1") (pintype "passive"))
      (node (ref "FB4") (pin "1") (pinfunction "1_1") (pintype "passive"))
      (node (ref "J1") (pin "10") (pinfunction "10_10") (pintype "passive"))
      (node (ref "J1") (pin "12") (pinfunction "12_12") (pintype "passive"))
      (node (ref "J1") (pin "14") (pinfunction "14_14") (pintype "passive"))
      (node (ref "J1") (pin "16") (pinfunction "16_16") (pintype "passive"))
      (node (ref "J1") (pin "18") (pinfunction "18_18") (pintype "passive"))
      (node (ref "J1") (pin "20") (pinfunction "20_20") (pintype "passive"))
      (node (ref "J1") (pin "4") (pinfunction "4_4") (pintype "passive"))
      (node (ref "J1") (pin "6") (pinfunction "6_6") (pintype "passive"))
      (node (ref "J1") (pin "8") (pinfunction "8_8") (pintype "passive"))
      (node (ref "J2") (pin "5") (pinfunction "GND_5") (pintype "passive"))
      (node (ref "J3") (pin "5") (pinfunction "GND_5") (pintype "passive"))
      (node (ref "J4") (pin "10") (pinfunction "CGND_10") (pintype "passive"))
      (node (ref "J4") (pin "11") (pinfunction "CGND_11") (pintype "passive"))
      (node (ref "J4") (pin "12") (pinfunction "CGND_12") (pintype "passive"))
      (node (ref "J4") (pin "6") (pinfunction "GND_6") (pintype "passive"))
      (node (ref "J4") (pin "9") (pinfunction "CGND_9") (pintype "passive"))
      (node (ref "R13") (pin "1") (pinfunction "1_1") (pintype "passive"))
      (node (ref "SW1") (pin "1") (pintype "passive"))
      (node (ref "SW1") (pin "4") (pintype "passive"))
      (node (ref "SW2") (pin "1") (pintype "passive"))
      (node (ref "SW2") (pin "4") (pintype "passive"))
      (node (ref "U1") (pin "1") (pinfunction "VSS_1") (pintype "passive"))
      (node (ref "U1") (pin "14") (pinfunction "VSS_14") (pintype "passive"))
      (node (ref "U1") (pin "24") (pinfunction "C_24") (pintype "passive"))
      (node (ref "U2") (pin "29") (pinfunction "GND_29") (pintype "passive"))
      (node (ref "U2") (pin "3") (pinfunction "GND_3") (pintype "passive"))
      (node (ref "U4") (pin "15") (pinfunction "VREFN_15") (pintype "passive"))
      (node (ref "U4") (pin "31") (pinfunction "VSS_31") (pintype "passive"))
      (node (ref "U4") (pin "41") (pinfunction "VSS_41") (pintype "passive"))
      (node (ref "U4") (pin "55") (pinfunction "VSS_55") (pintype "passive"))
      (node (ref "U4") (pin "72") (pinfunction "VSS_72") (pintype "passive"))
      (node (ref "U4") (pin "83") (pinfunction "VSS_83") (pintype "passive"))
      (node (ref "U4") (pin "97") (pinfunction "VSS_97") (pintype "passive"))
      (node (ref "U6") (pin "1") (pinfunction "A0_1") (pintype "passive"))
      (node (ref "U6") (pin "2") (pinfunction "A1_2") (pintype "passive"))
      (node (ref "U6") (pin "3") (pinfunction "A2_3") (pintype "passive"))
      (node (ref "U6") (pin "4") (pinfunction "GND_4") (pintype "passive"))
      (node (ref "U6") (pin "7") (pinfunction "WP_7") (pintype "passive"))
    )
    (net (code "51") (name "GNDA") (class "Default")
      (node (ref "C12") (pin "2") (pinfunction "2_2") (pintype "passive"))
      (node (ref "C8") (pin "1") (pinfunction "1_1") (pintype "passive"))
      (node (ref "FB3") (pin "2") (pinfunction "2_2") (pintype "passive"))
      (node (ref "R23") (pin "1") (pinfunction "1_1") (pintype "passive"))
      (node (ref "R28") (pin "1") (pinfunction "1_1") (pintype "passive"))
      (node (ref "SPK1") (pin "2") (pinfunction "-_2") (pintype "passive"))
      (node (ref "U3") (pin "2") (pinfunction "A_2") (pintype "passive"))
      (node (ref "U4") (pin "11") (pinfunction "VSSA_11") (pintype "passive"))
      (node (ref "U5") (pin "2") (pinfunction "V-_2") (pintype "passive"))
      (node (ref "U5") (pin "4") (pinfunction "GND_4") (pintype "passive"))
    )
    (net (code "52") (name "Net-(C9-Pad2)") (class "Default")
      (node (ref "C9") (pin "2") (pinfunction "2_2") (pintype "passive"))
      (node (ref "R23") (pin "2") (pinfunction "2_2") (pintype "passive"))
    )
    (net (code "53") (name "Net-(C10-Pad2)") (class "Default")
      (node (ref "C10") (pin "2") (pinfunction "2_2") (pintype "passive"))
      (node (ref "C11") (pin "1") (pinfunction "1_1") (pintype "passive"))
      (node (ref "U5") (pin "5") (pintype "passive"))
    )
    (net (code "54") (name "Net-(C11-Pad2)") (class "Default")
      (node (ref "C11") (pin "2") (pinfunction "2_2") (pintype "passive"))
      (node (ref "C13") (pin "1") (pinfunction "1_1") (pintype "passive"))
    )
    (net (code "55") (name "Net-(C13-Pad2)") (class "Default")
      (node (ref "C13") (pin "2") (pinfunction "2_2") (pintype "passive"))
      (node (ref "R28") (pin "2") (pinfunction "2_2") (pintype "passive"))
    )
    (net (code "56") (name "Net-(D1-A)") (class "Default")
      (node (ref "D1") (pin "1") (pinfunction "A_1") (pintype "passive"))
      (node (ref "J3") (pin "1") (pinfunction "VBUS_1") (pintype "passive"))
      (node (ref "R17") (pin "2") (pinfunction "2_2") (pintype "passive"))
    )
    (net (code "57") (name "Net-(D2-A)") (class "Default")
      (node (ref "D2") (pin "1") (pinfunction "A_1") (pintype "passive"))
      (node (ref "R7") (pin "1") (pinfunction "1_1") (pintype "passive"))
    )
    (net (code "58") (name "Net-(D3-A)") (class "Default")
      (node (ref "D3") (pin "1") (pinfunction "A_1") (pintype "passive"))
      (node (ref "R8") (pin "1") (pinfunction "1_1") (pintype "passive"))
    )
    (net (code "59") (name "Net-(D4-A)") (class "Default")
      (node (ref "D4") (pin "1") (pinfunction "A_1") (pintype "passive"))
      (node (ref "R9") (pin "1") (pinfunction "1_1") (pintype "passive"))
    )
    (net (code "60") (name "Net-(D5-A)") (class "Default")
      (node (ref "D5") (pin "1") (pinfunction "A_1") (pintype "passive"))
      (node (ref "R10") (pin "1") (pinfunction "1_1") (pintype "passive"))
    )
    (net (code "61") (name "Net-(D6-A)") (class "Default")
      (node (ref "D6") (pin "1") (pinfunction "A_1") (pintype "passive"))
      (node (ref "R11") (pin "1") (pinfunction "1_1") (pintype "passive"))
    )
    (net (code "62") (name "Net-(D11-K)") (class "Default")
      (node (ref "D11") (pin "2") (pinfunction "K_2") (pintype "passive"))
      (node (ref "J3") (pin "2") (pinfunction "D-_2") (pintype "passive"))
      (node (ref "R18") (pin "2") (pinfunction "2_2") (pintype "passive"))
    )
    (net (code "63") (name "Net-(D12-K)") (class "Default")
      (node (ref "D12") (pin "2") (pinfunction "K_2") (pintype "passive"))
      (node (ref "J3") (pin "3") (pinfunction "D+_3") (pintype "passive"))
      (node (ref "R16") (pin "1") (pinfunction "1_1") (pintype "passive"))
      (node (ref "R19") (pin "2") (pinfunction "2_2") (pintype "passive"))
    )
    (net (code "64") (name "Net-(D13-K)") (class "Default")
      (node (ref "C9") (pin "1") (pinfunction "1_1") (pintype "passive"))
      (node (ref "D13") (pin "2") (pinfunction "K_2") (pintype "passive"))
      (node (ref "D14") (pin "2") (pinfunction "K_2") (pintype "passive"))
    )
    (net (code "65") (name "Net-(FB1-Pad2)") (class "Default")
      (node (ref "FB1") (pin "2") (pinfunction "2_2") (pintype "passive"))
      (node (ref "J2") (pin "6") (pinfunction "CGND_6") (pintype "passive"))
      (node (ref "J2") (pin "7") (pinfunction "CGND_7") (pintype "passive"))
      (node (ref "J2") (pin "8") (pinfunction "CGND_8") (pintype "passive"))
      (node (ref "J2") (pin "9") (pinfunction "CGND_9") (pintype "passive"))
    )
    (net (code "66") (name "Net-(FB4-Pad2)") (class "Default")
      (node (ref "FB4") (pin "2") (pinfunction "2_2") (pintype "passive"))
      (node (ref "J3") (pin "6") (pinfunction "CGND_6") (pintype "passive"))
      (node (ref "J3") (pin "7") (pinfunction "CGND_7") (pintype "passive"))
      (node (ref "J3") (pin "8") (pinfunction "CGND_8") (pintype "passive"))
      (node (ref "J3") (pin "9") (pinfunction "CGND_9") (pintype "passive"))
    )
    (net (code "67") (name "Net-(J1-Pad1)") (class "Default")
      (node (ref "J1") (pin "1") (pinfunction "1_1") (pintype "passive"))
      (node (ref "R6") (pin "1") (pinfunction "1_1") (pintype "passive"))
    )
    (net (code "68") (name "Net-(Q1-C)") (class "Default")
      (node (ref "Q1") (pin "3") (pinfunction "C_3") (pintype "passive"))
      (node (ref "R16") (pin "2") (pinfunction "2_2") (pintype "passive"))
    )
    (net (code "69") (name "Net-(SPK1-+)") (class "Default")
      (node (ref "C10") (pin "1") (pinfunction "1_1") (pintype "passive"))
      (node (ref "SPK1") (pin "1") (pinfunction "+_1") (pintype "passive"))
    )
    (net (code "70") (name "Net-(U4-RTCX1)") (class "Default")
      (node (ref "C4") (pin "1") (pinfunction "1_1") (pintype "passive"))
      (node (ref "R21") (pin "1") (pinfunction "1_1") (pintype "passive"))
      (node (ref "U4") (pin "16") (pinfunction "RTCX1_16") (pintype "passive"))
      (node (ref "X1") (pin "1") (pinfunction "1_1") (pintype "passive"))
    )
    (net (code "71") (name "Net-(U4-RTCX2)") (class "Default")
      (node (ref "C5") (pin "1") (pinfunction "1_1") (pintype "passive"))
      (node (ref "R21") (pin "2") (pinfunction "2_2") (pintype "passive"))
      (node (ref "U4") (pin "18") (pinfunction "RTCX2_18") (pintype "passive"))
      (node (ref "X1") (pin "2") (pinfunction "2_2") (pintype "passive"))
    )
    (net (code "72") (name "Net-(U4-XTAL1)") (class "Default")
      (node (ref "C6") (pin "1") (pinfunction "1_1") (pintype "passive"))
      (node (ref "R22") (pin "1") (pinfunction "1_1") (pintype "passive"))
      (node (ref "U4") (pin "22") (pinfunction "XTAL1_22") (pintype "passive"))
      (node (ref "X2") (pin "1") (pinfunction "1_1") (pintype "passive"))
    )
    (net (code "73") (name "Net-(U4-XTAL2)") (class "Default")
      (node (ref "C7") (pin "1") (pinfunction "1_1") (pintype "passive"))
      (node (ref "R22") (pin "2") (pinfunction "2_2") (pintype "passive"))
      (node (ref "U4") (pin "23") (pinfunction "XTAL2_23") (pintype "passive"))
      (node (ref "X2") (pin "2") (pinfunction "2_2") (pintype "passive"))
    )
    (net (code "74") (name "Net-(U5-BYP)") (class "Default")
      (node (ref "C12") (pin "1") (pinfunction "1_1") (pintype "passive"))
      (node (ref "U5") (pin "7") (pinfunction "BYP_7") (pintype "passive"))
    )
    (net (code "75") (name "Net-(U5-V+)") (class "Default")
      (node (ref "R23") (pin "3") (pintype "passive"))
      (node (ref "U5") (pin "3") (pinfunction "V+_3") (pintype "passive"))
    )
    (net (code "76") (name "VBL") (class "Default")
      (node (ref "U1") (pin "23") (pinfunction "A_23") (pintype "passive"))
    )
    (net (code "77") (name "VCC") (class "Default")
      (node (ref "C8") (pin "2") (pinfunction "2_2") (pintype "passive"))
      (node (ref "U5") (pin "6") (pinfunction "VS_6") (pintype "passive"))
    )
    (net (code "78") (name "VUSB") (class "Default")
      (node (ref "D1") (pin "2") (pinfunction "K_2") (pintype "passive"))
      (node (ref "J2") (pin "1") (pinfunction "VBUS_1") (pintype "passive"))
      (node (ref "R12") (pin "2") (pinfunction "2_2") (pintype "passive"))
      (node (ref "U2") (pin "7") (pinfunction "REGIN_7") (pintype "passive"))
      (node (ref "U2") (pin "8") (pinfunction "VBUS_8") (pintype "passive"))
    )
    (net (code "79") (name "unconnected-(J1-Pad2)") (class "Default")
      (node (ref "J1") (pin "2") (pinfunction "2_2") (pintype "passive"))
    )
    (net (code "80") (name "unconnected-(J1-Pad3)") (class "Default")
      (node (ref "J1") (pin "3") (pinfunction "3_3") (pintype "passive"))
    )
    (net (code "81") (name "unconnected-(J1-Pad11)") (class "Default")
      (node (ref "J1") (pin "11") (pinfunction "11_11") (pintype "passive"))
    )
    (net (code "82") (name "unconnected-(J1-Pad15)") (class "Default")
      (node (ref "J1") (pin "15") (pinfunction "15_15") (pintype "passive"))
    )
    (net (code "83") (name "unconnected-(J1-Pad17)") (class "Default")
      (node (ref "J1") (pin "17") (pinfunction "17_17") (pintype "passive"))
    )
    (net (code "84") (name "unconnected-(J1-Pad19)") (class "Default")
      (node (ref "J1") (pin "19") (pinfunction "19_19") (pintype "passive"))
    )
    (net (code "85") (name "unconnected-(J2-ID-Pad4)") (class "Default")
      (node (ref "J2") (pin "4") (pinfunction "ID_4") (pintype "passive"))
    )
    (net (code "86") (name "unconnected-(J3-ID-Pad4)") (class "Default")
      (node (ref "J3") (pin "4") (pinfunction "ID_4") (pintype "passive"))
    )
    (net (code "87") (name "unconnected-(J4-NC{slash}DAT1-Pad8)") (class "Default")
      (node (ref "J4") (pin "8") (pinfunction "NC/DAT1_8") (pintype "passive"))
    )
    (net (code "88") (name "unconnected-(J4-NC{slash}DAT2-Pad1)") (class "Default")
      (node (ref "J4") (pin "1") (pinfunction "NC/DAT2_1") (pintype "passive"))
    )
    (net (code "89") (name "unconnected-(U1-NC-Pad8)") (class "Default")
      (node (ref "U1") (pin "8") (pinfunction "NC_8") (pintype "passive"))
    )
    (net (code "90") (name "unconnected-(U1-NC-Pad9)") (class "Default")
      (node (ref "U1") (pin "9") (pinfunction "NC_9") (pintype "passive"))
    )
    (net (code "91") (name "unconnected-(U1-NC-Pad10)") (class "Default")
      (node (ref "U1") (pin "10") (pinfunction "NC_10") (pintype "passive"))
    )
    (net (code "92") (name "unconnected-(U1-NC-Pad11)") (class "Default")
      (node (ref "U1") (pin "11") (pinfunction "NC_11") (pintype "passive"))
    )
    (net (code "93") (name "unconnected-(U1-NC-Pad12)") (class "Default")
      (node (ref "U1") (pin "12") (pinfunction "NC_12") (pintype "passive"))
    )
    (net (code "94") (name "unconnected-(U1-NC-Pad13)") (class "Default")
      (node (ref "U1") (pin "13") (pinfunction "NC_13") (pintype "passive"))
    )
    (net (code "95") (name "unconnected-(U1-NC-Pad16)") (class "Default")
      (node (ref "U1") (pin "16") (pinfunction "NC_16") (pintype "passive"))
    )
    (net (code "96") (name "unconnected-(U1-NC-Pad17)") (class "Default")
      (node (ref "U1") (pin "17") (pinfunction "NC_17") (pintype "passive"))
    )
    (net (code "97") (name "unconnected-(U1-NC-Pad18)") (class "Default")
      (node (ref "U1") (pin "18") (pinfunction "NC_18") (pintype "passive"))
    )
    (net (code "98") (name "unconnected-(U1-NC-Pad19)") (class "Default")
      (node (ref "U1") (pin "19") (pinfunction "NC_19") (pintype "passive"))
    )
    (net (code "99") (name "unconnected-(U1-NC-Pad20)") (class "Default")
      (node (ref "U1") (pin "20") (pinfunction "NC_20") (pintype "passive"))
    )
    (net (code "100") (name "unconnected-(U1-NC-Pad21)") (class "Default")
      (node (ref "U1") (pin "21") (pinfunction "NC_21") (pintype "passive"))
    )
    (net (code "101") (name "unconnected-(U1-NC-Pad22)") (class "Default")
      (node (ref "U1") (pin "22") (pinfunction "NC_22") (pintype "passive"))
    )
    (net (code "102") (name "unconnected-(U1-RES-Pad4)") (class "Default")
      (node (ref "U1") (pin "4") (pinfunction "RES_4") (pintype "passive"))
    )
    (net (code "103") (name "unconnected-(U1-VCI-Pad3)") (class "Default")
      (node (ref "U1") (pin "3") (pinfunction "VCI_3") (pintype "passive"))
    )
    (net (code "104") (name "unconnected-(U2-CTS-Pad23)") (class "Default")
      (node (ref "U2") (pin "23") (pinfunction "CTS_23") (pintype "passive"))
    )
    (net (code "105") (name "unconnected-(U2-DCD-Pad1)") (class "Default")
      (node (ref "U2") (pin "1") (pinfunction "DCD_1") (pintype "passive"))
    )
    (net (code "106") (name "unconnected-(U2-DSR-Pad27)") (class "Default")
      (node (ref "U2") (pin "27") (pinfunction "DSR_27") (pintype "passive"))
    )
    (net (code "107") (name "unconnected-(U2-DTR-Pad28)") (class "Default")
      (node (ref "U2") (pin "28") (pinfunction "DTR_28") (pintype "passive"))
    )
    (net (code "108") (name "unconnected-(U2-NC-Pad10)") (class "Default")
      (node (ref "U2") (pin "10") (pinfunction "NC_10") (pintype "passive"))
    )
    (net (code "109") (name "unconnected-(U2-NC-Pad13)") (class "Default")
      (node (ref "U2") (pin "13") (pinfunction "NC_13") (pintype "passive"))
    )
    (net (code "110") (name "unconnected-(U2-NC-Pad14)") (class "Default")
      (node (ref "U2") (pin "14") (pinfunction "NC_14") (pintype "passive"))
    )
    (net (code "111") (name "unconnected-(U2-NC-Pad15)") (class "Default")
      (node (ref "U2") (pin "15") (pinfunction "NC_15") (pintype "passive"))
    )
    (net (code "112") (name "unconnected-(U2-NC-Pad16)") (class "Default")
      (node (ref "U2") (pin "16") (pinfunction "NC_16") (pintype "passive"))
    )
    (net (code "113") (name "unconnected-(U2-NC-Pad17)") (class "Default")
      (node (ref "U2") (pin "17") (pinfunction "NC_17") (pintype "passive"))
    )
    (net (code "114") (name "unconnected-(U2-NC-Pad18)") (class "Default")
      (node (ref "U2") (pin "18") (pinfunction "NC_18") (pintype "passive"))
    )
    (net (code "115") (name "unconnected-(U2-NC-Pad19)") (class "Default")
      (node (ref "U2") (pin "19") (pinfunction "NC_19") (pintype "passive"))
    )
    (net (code "116") (name "unconnected-(U2-NC-Pad20)") (class "Default")
      (node (ref "U2") (pin "20") (pinfunction "NC_20") (pintype "passive"))
    )
    (net (code "117") (name "unconnected-(U2-NC-Pad21)") (class "Default")
      (node (ref "U2") (pin "21") (pinfunction "NC_21") (pintype "passive"))
    )
    (net (code "118") (name "unconnected-(U2-NC-Pad22)") (class "Default")
      (node (ref "U2") (pin "22") (pinfunction "NC_22") (pintype "passive"))
    )
    (net (code "119") (name "unconnected-(U2-RI-Pad2)") (class "Default")
      (node (ref "U2") (pin "2") (pinfunction "RI_2") (pintype "passive"))
    )
    (net (code "120") (name "unconnected-(U2-RTS-Pad24)") (class "Default")
      (node (ref "U2") (pin "24") (pinfunction "RTS_24") (pintype "passive"))
    )
    (net (code "121") (name "unconnected-(U2-SUSPEND-Pad11)") (class "Default")
      (node (ref "U2") (pin "11") (pinfunction "SUSPEND_11") (pintype "passive"))
    )
    (net (code "122") (name "unconnected-(U4-NC-Pad13)") (class "Default")
      (node (ref "U4") (pin "13") (pinfunction "NC_13") (pintype "passive"))
    )
    (net (code "123") (name "unconnected-(U4-P0:4-Pad81)") (class "Default")
      (node (ref "U4") (pin "81") (pinfunction "P0:4_81") (pintype "passive"))
    )
    (net (code "124") (name "unconnected-(U4-P0:5-Pad80)") (class "Default")
      (node (ref "U4") (pin "80") (pinfunction "P0:5_80") (pintype "passive"))
    )
    (net (code "125") (name "unconnected-(U4-P0:10-Pad48)") (class "Default")
      (node (ref "U4") (pin "48") (pinfunction "P0:10_48") (pintype "passive"))
    )
    (net (code "126") (name "unconnected-(U4-P0:11-Pad49)") (class "Default")
      (node (ref "U4") (pin "49") (pinfunction "P0:11_49") (pintype "passive"))
    )
    (net (code "127") (name "unconnected-(U4-P0:19-Pad59)") (class "Default")
      (node (ref "U4") (pin "59") (pinfunction "P0:19_59") (pintype "passive"))
    )
    (net (code "128") (name "unconnected-(U4-P0:20-Pad58)") (class "Default")
      (node (ref "U4") (pin "58") (pinfunction "P0:20_58") (pintype "passive"))
    )
    (net (code "129") (name "unconnected-(U4-P0:21-Pad57)") (class "Default")
      (node (ref "U4") (pin "57") (pinfunction "P0:21_57") (pintype "passive"))
    )
    (net (code "130") (name "unconnected-(U4-P0:22-Pad56)") (class "Default")
      (node (ref "U4") (pin "56") (pinfunction "P0:22_56") (pintype "passive"))
    )
    (net (code "131") (name "unconnected-(U4-P1:0-Pad95)") (class "Default")
      (node (ref "U4") (pin "95") (pinfunction "P1:0_95") (pintype "passive"))
    )
    (net (code "132") (name "unconnected-(U4-P1:14-Pad89)") (class "Default")
      (node (ref "U4") (pin "89") (pinfunction "P1:14_89") (pintype "passive"))
    )
    (net (code "133") (name "unconnected-(U4-P1:15-Pad88)") (class "Default")
      (node (ref "U4") (pin "88") (pinfunction "P1:15_88") (pintype "passive"))
    )
    (net (code "134") (name "unconnected-(U4-P1:16-Pad87)") (class "Default")
      (node (ref "U4") (pin "87") (pinfunction "P1:16_87") (pintype "passive"))
    )
    (net (code "135") (name "unconnected-(U4-P1:17-Pad86)") (class "Default")
      (node (ref "U4") (pin "86") (pinfunction "P1:17_86") (pintype "passive"))
    )
    (net (code "136") (name "unconnected-(U4-P1:23-Pad37)") (class "Default")
      (node (ref "U4") (pin "37") (pinfunction "P1:23_37") (pintype "passive"))
    )
    (net (code "137") (name "unconnected-(U4-P1:24-Pad38)") (class "Default")
      (node (ref "U4") (pin "38") (pinfunction "P1:24_38") (pintype "passive"))
    )
    (net (code "138") (name "unconnected-(U4-P1:25-Pad39)") (class "Default")
      (node (ref "U4") (pin "39") (pinfunction "P1:25_39") (pintype "passive"))
    )
    (net (code "139") (name "unconnected-(U4-P1:26-Pad40)") (class "Default")
      (node (ref "U4") (pin "40") (pinfunction "P1:26_40") (pintype "passive"))
    )
    (net (code "140") (name "unconnected-(U4-P1:27-Pad43)") (class "Default")
      (node (ref "U4") (pin "43") (pinfunction "P1:27_43") (pintype "passive"))
    )
    (net (code "141") (name "unconnected-(U4-P1:28-Pad44)") (class "Default")
      (node (ref "U4") (pin "44") (pinfunction "P1:28_44") (pintype "passive"))
    )
    (net (code "142") (name "unconnected-(U4-P1:29-Pad45)") (class "Default")
      (node (ref "U4") (pin "45") (pinfunction "P1:29_45") (pintype "passive"))
    )
    (net (code "143") (name "unconnected-(U4-P1:31-Pad20)") (class "Default")
      (node (ref "U4") (pin "20") (pinfunction "P1:31_20") (pintype "passive"))
    )
    (net (code "144") (name "unconnected-(U4-P2:0-Pad75)") (class "Default")
      (node (ref "U4") (pin "75") (pinfunction "P2:0_75") (pintype "passive"))
    )
    (net (code "145") (name "unconnected-(U4-P2:1-Pad74)") (class "Default")
      (node (ref "U4") (pin "74") (pinfunction "P2:1_74") (pintype "passive"))
    )
    (net (code "146") (name "unconnected-(U4-P2:2-Pad73)") (class "Default")
      (node (ref "U4") (pin "73") (pinfunction "P2:2_73") (pintype "passive"))
    )
    (net (code "147") (name "unconnected-(U4-P2:3-Pad70)") (class "Default")
      (node (ref "U4") (pin "70") (pinfunction "P2:3_70") (pintype "passive"))
    )
    (net (code "148") (name "unconnected-(U4-P2:5-Pad68)") (class "Default")
      (node (ref "U4") (pin "68") (pinfunction "P2:5_68") (pintype "passive"))
    )
    (net (code "149") (name "unconnected-(U4-P2:6-Pad67)") (class "Default")
      (node (ref "U4") (pin "67") (pinfunction "P2:6_67") (pintype "passive"))
    )
    (net (code "150") (name "unconnected-(U4-P2:7-Pad66)") (class "Default")
      (node (ref "U4") (pin "66") (pinfunction "P2:7_66") (pintype "passive"))
    )
    (net (code "151") (name "unconnected-(U4-P2:8-Pad65)") (class "Default")
      (node (ref "U4") (pin "65") (pinfunction "P2:8_65") (pintype "passive"))
    )
    (net (code "152") (name "unconnected-(U4-P2:13-Pad50)") (class "Default")
      (node (ref "U4") (pin "50") (pinfunction "P2:13_50") (pintype "passive"))
    )
    (net (code "153") (name "unconnected-(U4-P2:69-Pad69)") (class "Default")
      (node (ref "U4") (pin "69") (pinfunction "P2:69_69") (pintype "passive"))
    )
    (net (code "154") (name "unconnected-(U4-P4:28-Pad82)") (class "Default")
      (node (ref "U4") (pin "82") (pinfunction "P4:28_82") (pintype "passive"))
    )
    (net (code "155") (name "unconnected-(U4-P4:29-Pad85)") (class "Default")
      (node (ref "U4") (pin "85") (pinfunction "P4:29_85") (pintype "passive"))
    )
    (net (code "156") (name "unconnected-(U4-RTCK-Pad100)") (class "Default")
      (node (ref "U4") (pin "100") (pinfunction "RTCK_100") (pintype "passive"))
    )
    (net (code "157") (name "unconnected-(U5-AG-Pad1)") (class "Default")
      (node (ref "U5") (pin "1") (pinfunction "AG_1") (pintype "passive"))
    )
    (net (code "158") (name "unconnected-(U5-AG-Pad8)") (class "Default")
      (node (ref "U5") (pin "8") (pinfunction "AG_8") (pintype "passive"))
    )
  )
)
